# AC-DC_Power_supply.net
KiCad netlist of a schematic drawn in Altium Designer
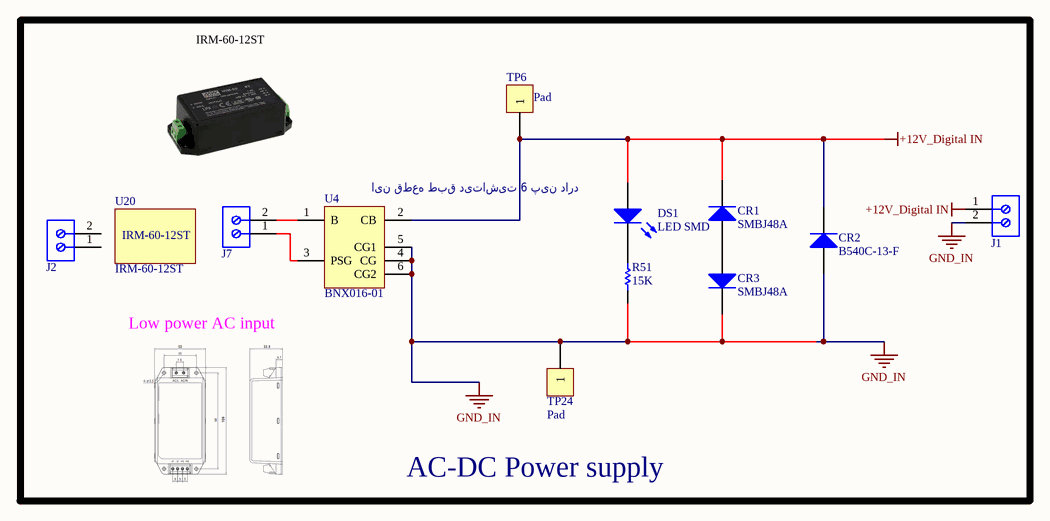
[diagram p0: AC-DC Power supply.SchDoc]

(export (version "E")
  (design (tool "Eeschema 10.0.6"))
  (components
    (comp (ref "CR1")
      (value "SMBJ48A")
      (footprint "Buck:SMB (DO-214AA)")
      (libsource (lib "MYLIB") (part "DiodeSMD4.5mm"))
    )
    (comp (ref "CR2")
      (value "B540C-13-F")
      (footprint "Buck:SMC (DO-214AB)")
      (libsource (lib "MYLIB") (part "DiodeSMD5.5mm"))
    )
    (comp (ref "CR3")
      (value "SMBJ48A")
      (footprint "Buck:SMB (DO-214AA)")
      (libsource (lib "MYLIB") (part "DiodeSMD4.5mm"))
    )
    (comp (ref "DS1") (value "LED SMD") (footprint "Buck:LED0805") (libsource (lib "MYLIB") (part "LED SMD")))
    (comp (ref "J1")
      (value "691101710002")
      (footprint "Buck:691101710002")
      (description "WR-TBL Series 101 Horizontal Entry Modular, THT, pitch 5mm, 2p")
      (fields (field (name "MANUFACTURER") "Wurth Elektronik"))
      (libsource (lib "Altium_WR-TBL (rev22b)") (part "691101710002"))
    )
    (comp (ref "J2")
      (value "691101710002")
      (footprint "Buck:691101710002")
      (description "WR-TBL Series 101 Horizontal Entry Modular, THT, pitch 5mm, 2p")
      (fields (field (name "MANUFACTURER") "Wurth Elektronik"))
      (libsource (lib "Altium_WR-TBL (rev22b)") (part "691101710002"))
    )
    (comp (ref "J7")
      (value "691101710002")
      (footprint "Buck:691101710002")
      (description "WR-TBL Series 101 Horizontal Entry Modular, THT, pitch 5mm, 2p")
      (fields (field (name "MANUFACTURER") "Wurth Elektronik"))
      (libsource (lib "Altium_WR-TBL (rev22b)") (part "691101710002"))
    )
    (comp (ref "R51") (value "15K") (footprint "Buck:R0805") (libsource (lib "MYLIB") (part "ResSMD")))
    (comp (ref "TP6")
      (value "Pad")
      (footprint "Buck:TP-0.5mm")
      (libsource (lib "MYLIB") (part "Con1 pin-Small"))
    )
    (comp (ref "TP24")
      (value "Pad")
      (footprint "Buck:TP-0.5mm")
      (libsource (lib "") (part "Con1 pin-Small_1"))
    )
    (comp (ref "U4")
      (value "BNX016-01")
      (footprint "Buck:BNX016")
      (libsource (lib "AC-DC Power supply") (part "BNX016"))
    )
    (comp (ref "U20")
      (value "IRM-60-12ST")
      (footprint "Buck:IRM-60-12ST")
      (libsource (lib "AC-DC Power supply") (part "IRM-60-12ST"))
    )
  )
  (nets
    (net (code "1") (name "+12V_Digital IN") (class "Default")
      (node (ref "CR1") (pin "2") (pinfunction "K_2") (pintype "passive"))
      (node (ref "CR2") (pin "K") (pinfunction "K_K") (pintype "passive"))
      (node (ref "DS1") (pin "1") (pinfunction "A_1") (pintype "passive"))
      (node (ref "J1") (pin "1") (pinfunction "1_1") (pintype "passive"))
      (node (ref "TP6") (pin "1") (pinfunction "1_1") (pintype "passive"))
      (node (ref "U4") (pin "2") (pinfunction "CB_2") (pintype "passive"))
    )
    (net (code "2") (name "GND_IN") (class "Default")
      (node (ref "CR2") (pin "A") (pinfunction "A_A") (pintype "passive"))
      (node (ref "CR3") (pin "2") (pinfunction "K_2") (pintype "passive"))
      (node (ref "J1") (pin "2") (pinfunction "2_2") (pintype "passive"))
      (node (ref "R51") (pin "2") (pinfunction "2_2") (pintype "passive"))
      (node (ref "TP24") (pin "1") (pinfunction "1_1") (pintype "passive"))
      (node (ref "U4") (pin "4") (pinfunction "CG_4") (pintype "passive"))
      (node (ref "U4") (pin "5") (pinfunction "CG1_5") (pintype "passive"))
      (node (ref "U4") (pin "6") (pinfunction "CG2_6") (pintype "passive"))
    )
    (net (code "3") (name "Net-(CR1-A)") (class "Default")
      (node (ref "CR1") (pin "1") (pinfunction "A_1") (pintype "passive"))
      (node (ref "CR3") (pin "1") (pinfunction "A_1") (pintype "passive"))
    )
    (net (code "4") (name "Net-(DS1-K)") (class "Default")
      (node (ref "DS1") (pin "2") (pinfunction "K_2") (pintype "passive"))
      (node (ref "R51") (pin "1") (pinfunction "1_1") (pintype "passive"))
    )
    (net (code "5") (name "Net-(U4-B)") (class "Default")
      (node (ref "J7") (pin "2") (pinfunction "2_2") (pintype "passive"))
      (node (ref "U4") (pin "1") (pinfunction "B_1") (pintype "passive"))
    )
    (net (code "6") (name "Net-(U4-PSG)") (class "Default")
      (node (ref "J7") (pin "1") (pinfunction "1_1") (pintype "passive"))
      (node (ref "U4") (pin "3") (pinfunction "PSG_3") (pintype "passive"))
    )
    (net (code "7") (name "unconnected-(J2-Pad1)") (class "Default")
      (node (ref "J2") (pin "1") (pinfunction "1_1") (pintype "passive"))
    )
    (net (code "8") (name "unconnected-(J2-Pad2)") (class "Default")
      (node (ref "J2") (pin "2") (pinfunction "2_2") (pintype "passive"))
    )
    (net (code "9") (name "unconnected-(U4-Pad5)") (class "Default")
      (node (ref "U4") (pin "5") (pinfunction "5_5") (pintype "passive"))
    )
    (net (code "10") (name "unconnected-(U4-Pad6)") (class "Default")
      (node (ref "U4") (pin "6") (pinfunction "6_6") (pintype "passive"))
    )
    (net (code "11") (name "unconnected-(U20-Pad5)") (class "Default")
      (node (ref "U20") (pin "5") (pinfunction "5_5") (pintype "passive"))
    )
    (net (code "12") (name "unconnected-(U20-Pad6)") (class "Default")
      (node (ref "U20") (pin "6") (pinfunction "6_6") (pintype "passive"))
    )
  )
)
